# ChargeContactBoard.net
KiCad netlist of a schematic drawn in Altium Designer
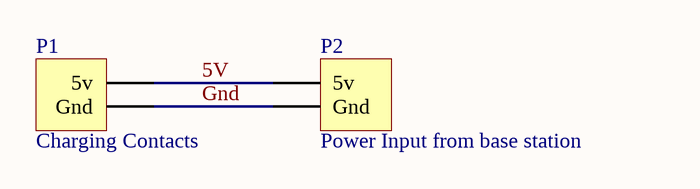
[diagram p0: ChargeContactBoard.SchDoc]

(export (version "E")
  (design (tool "Eeschema 10.0.6"))
  (components
    (comp (ref "P1")
      (value "Charging Contacts")
      (footprint "Modular 2pin contact")
      (description "Header, 2-Pin")
      (fields (field (name "PUBLISHER") "Altium Limited"))
      (libsource (lib "") (part "Header 2_1"))
    )
    (comp (ref "P2")
      (value "Power Input from base station")
      (footprint "Charger Board Connector Male")
      (description "Header, 2-Pin")
      (fields (field (name "PUBLISHER") "Altium Limited"))
      (libsource (lib "Miscellaneous Connectors") (part "Header 2"))
    )
  )
  (nets
    (net (code "1") (name "/5V") (class "Default")
      (node (ref "P1") (pin "2") (pinfunction "5v_2") (pintype "passive"))
      (node (ref "P2") (pin "3") (pinfunction "5v_3") (pintype "passive"))
    )
    (net (code "2") (name "/Gnd") (class "Default")
      (node (ref "P1") (pin "1") (pinfunction "Gnd_1") (pintype "passive"))
      (node (ref "P2") (pin "2") (pinfunction "Gnd_2") (pintype "passive"))
    )
  )
)
